# usb-serial-socket.net
KiCad netlist of a schematic drawn in EAGLE
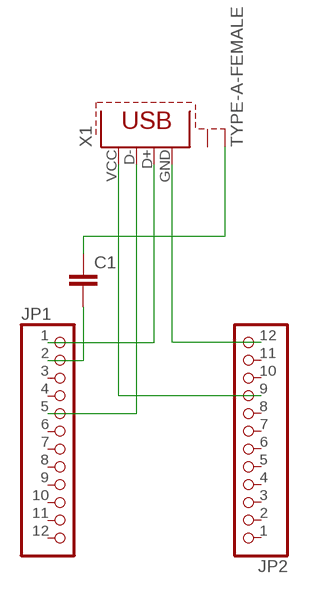
[diagram p0: schematic, sheet 1]

(export (version "E")
  (design (tool "Eeschema 10.0.6"))
  (components
    (comp (ref "C1")
      (value "C-EU025-024X044")
      (footprint "eagle-import:C025-024X044")
      (libsource (lib "eagle-import") (part "C-EU025-024X044"))
    )
    (comp (ref "JP1")
      (value "PINHD-1X12")
      (footprint "eagle-import:1X12")
      (libsource (lib "eagle-import") (part "PINHD-1X12"))
    )
    (comp (ref "JP2")
      (value "PINHD-1X12")
      (footprint "eagle-import:1X12")
      (libsource (lib "eagle-import") (part "PINHD-1X12"))
    )
    (comp (ref "X1")
      (value "TYPE-A-FEMALE")
      (footprint "eagle-import:TYPE-A-FEMALE")
      (libsource (lib "eagle-import") (part "TYPE-A-FEMALE"))
    )
  )
  (nets
    (net (code "1") (name "Net-(C1-Pad1)") (class "Default")
      (node (ref "C1") (pin "1") (pinfunction "1_1") (pintype "passive"))
      (node (ref "X1") (pin "S2") (pinfunction "S2_S2") (pintype "passive"))
    )
    (net (code "2") (name "Net-(C1-Pad2)") (class "Default")
      (node (ref "C1") (pin "2") (pinfunction "2_2") (pintype "passive"))
      (node (ref "JP1") (pin "2") (pinfunction "2_2") (pintype "passive"))
    )
    (net (code "3") (name "Net-(JP1-Pad1)") (class "Default")
      (node (ref "JP1") (pin "1") (pinfunction "1_1") (pintype "passive"))
      (node (ref "X1") (pin "D+") (pinfunction "D+_D+") (pintype "passive"))
    )
    (net (code "4") (name "Net-(JP1-Pad5)") (class "Default")
      (node (ref "JP1") (pin "5") (pinfunction "5_5") (pintype "passive"))
      (node (ref "X1") (pin "D-") (pinfunction "D-_D-") (pintype "passive"))
    )
    (net (code "5") (name "Net-(JP2-Pad9)") (class "Default")
      (node (ref "JP2") (pin "9") (pinfunction "9_9") (pintype "passive"))
      (node (ref "X1") (pin "VCC") (pinfunction "VCC_VCC") (pintype "passive"))
    )
    (net (code "6") (name "Net-(JP2-Pad12)") (class "Default")
      (node (ref "JP2") (pin "12") (pinfunction "12_12") (pintype "passive"))
      (node (ref "X1") (pin "GND") (pinfunction "GND_GND") (pintype "passive"))
    )
    (net (code "7") (name "unconnected-(JP1-Pad3)") (class "Default")
      (node (ref "JP1") (pin "3") (pinfunction "3_3") (pintype "passive"))
    )
    (net (code "8") (name "unconnected-(JP1-Pad4)") (class "Default")
      (node (ref "JP1") (pin "4") (pinfunction "4_4") (pintype "passive"))
    )
    (net (code "9") (name "unconnected-(JP1-Pad6)") (class "Default")
      (node (ref "JP1") (pin "6") (pinfunction "6_6") (pintype "passive"))
    )
    (net (code "10") (name "unconnected-(JP1-Pad7)") (class "Default")
      (node (ref "JP1") (pin "7") (pinfunction "7_7") (pintype "passive"))
    )
    (net (code "11") (name "unconnected-(JP1-Pad8)") (class "Default")
      (node (ref "JP1") (pin "8") (pinfunction "8_8") (pintype "passive"))
    )
    (net (code "12") (name "unconnected-(JP1-Pad9)") (class "Default")
      (node (ref "JP1") (pin "9") (pinfunction "9_9") (pintype "passive"))
    )
    (net (code "13") (name "unconnected-(JP1-Pad10)") (class "Default")
      (node (ref "JP1") (pin "10") (pinfunction "10_10") (pintype "passive"))
    )
    (net (code "14") (name "unconnected-(JP1-Pad11)") (class "Default")
      (node (ref "JP1") (pin "11") (pinfunction "11_11") (pintype "passive"))
    )
    (net (code "15") (name "unconnected-(JP1-Pad12)") (class "Default")
      (node (ref "JP1") (pin "12") (pinfunction "12_12") (pintype "passive"))
    )
    (net (code "16") (name "unconnected-(JP2-Pad1)") (class "Default")
      (node (ref "JP2") (pin "1") (pinfunction "1_1") (pintype "passive"))
    )
    (net (code "17") (name "unconnected-(JP2-Pad2)") (class "Default")
      (node (ref "JP2") (pin "2") (pinfunction "2_2") (pintype "passive"))
    )
    (net (code "18") (name "unconnected-(JP2-Pad3)") (class "Default")
      (node (ref "JP2") (pin "3") (pinfunction "3_3") (pintype "passive"))
    )
    (net (code "19") (name "unconnected-(JP2-Pad4)") (class "Default")
      (node (ref "JP2") (pin "4") (pinfunction "4_4") (pintype "passive"))
    )
    (net (code "20") (name "unconnected-(JP2-Pad5)") (class "Default")
      (node (ref "JP2") (pin "5") (pinfunction "5_5") (pintype "passive"))
    )
    (net (code "21") (name "unconnected-(JP2-Pad6)") (class "Default")
      (node (ref "JP2") (pin "6") (pinfunction "6_6") (pintype "passive"))
    )
    (net (code "22") (name "unconnected-(JP2-Pad7)") (class "Default")
      (node (ref "JP2") (pin "7") (pinfunction "7_7") (pintype "passive"))
    )
    (net (code "23") (name "unconnected-(JP2-Pad8)") (class "Default")
      (node (ref "JP2") (pin "8") (pinfunction "8_8") (pintype "passive"))
    )
    (net (code "24") (name "unconnected-(JP2-Pad10)") (class "Default")
      (node (ref "JP2") (pin "10") (pinfunction "10_10") (pintype "passive"))
    )
    (net (code "25") (name "unconnected-(JP2-Pad11)") (class "Default")
      (node (ref "JP2") (pin "11") (pinfunction "11_11") (pintype "passive"))
    )
    (net (code "26") (name "unconnected-(X1-PadS1)") (class "Default")
      (node (ref "X1") (pin "S1") (pinfunction "S1_S1") (pintype "passive"))
    )
  )
)
